# tiny_robot_renew.net
KiCad netlist of a schematic drawn in EAGLE
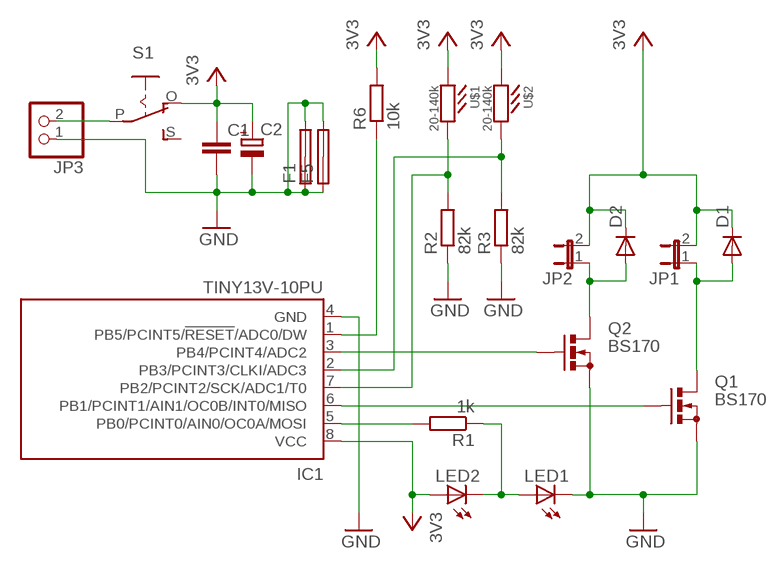
[diagram p0: schematic, sheet 1]

(export (version "E")
  (design (tool "Eeschema 10.0.6"))
  (components
    (comp (ref "C1")
      (value "C-EU025-025X050")
      (footprint "eagle-import:C025-025X050")
      (libsource (lib "eagle-import") (part "C-EU025-025X050"))
    )
    (comp (ref "C2")
      (value "CPOL-EUE2,5-6E")
      (footprint "eagle-import:E2,5-6E")
      (libsource (lib "eagle-import") (part "CPOL-EUE2,5-6E"))
    )
    (comp (ref "D1")
      (value "DIODE-D-2.5")
      (footprint "eagle-import:D-2.5")
      (libsource (lib "eagle-import") (part "DIODE-D-2.5"))
    )
    (comp (ref "D2")
      (value "DIODE-D-2.5")
      (footprint "eagle-import:D-2.5")
      (libsource (lib "eagle-import") (part "DIODE-D-2.5"))
    )
    (comp (ref "F1")
      (value "SHK20L")
      (footprint "eagle-import:SHK20L")
      (libsource (lib "eagle-import") (part "SHK20L"))
    )
    (comp (ref "F5")
      (value "SHK20Q")
      (footprint "eagle-import:SHK20Q")
      (libsource (lib "eagle-import") (part "SHK20Q"))
    )
    (comp (ref "IC1")
      (value "TINY13V-10PU")
      (footprint "eagle-import:DIL08")
      (fields (field (name "MPN") "ATTINY13V-10PU"))
      (libsource (lib "eagle-import") (part "TINY13PUV-10"))
    )
    (comp (ref "JP1")
      (value "JP1E")
      (footprint "eagle-import:JP1")
      (libsource (lib "eagle-import") (part "JP1E"))
    )
    (comp (ref "JP2")
      (value "JP1E")
      (footprint "eagle-import:JP1")
      (libsource (lib "eagle-import") (part "JP1E"))
    )
    (comp (ref "JP3")
      (value "PINHD-1X2")
      (footprint "eagle-import:1X02")
      (libsource (lib "eagle-import") (part "PINHD-1X2"))
    )
    (comp (ref "LED1")
      (value "LED3MM")
      (footprint "eagle-import:LED3MM")
      (libsource (lib "eagle-import") (part "LED3MM"))
    )
    (comp (ref "LED2")
      (value "LED3MM")
      (footprint "eagle-import:LED3MM")
      (libsource (lib "eagle-import") (part "LED3MM"))
    )
    (comp (ref "Q1")
      (value "BS170")
      (footprint "eagle-import:SOT54E")
      (libsource (lib "eagle-import") (part "BS170"))
    )
    (comp (ref "Q2")
      (value "BS170")
      (footprint "eagle-import:SOT54E")
      (libsource (lib "eagle-import") (part "BS170"))
    )
    (comp (ref "R1")
      (value "1k")
      (footprint "eagle-import:0204_7")
      (libsource (lib "eagle-import") (part "R-EU_0204/7"))
    )
    (comp (ref "R2")
      (value "82k")
      (footprint "eagle-import:0207_2V")
      (libsource (lib "eagle-import") (part "R-EU_0207/2V"))
    )
    (comp (ref "R3")
      (value "82k")
      (footprint "eagle-import:0207_2V")
      (libsource (lib "eagle-import") (part "R-EU_0207/2V"))
    )
    (comp (ref "R6")
      (value "10k")
      (footprint "eagle-import:0204_7")
      (libsource (lib "eagle-import") (part "R-EU_0204/7"))
    )
    (comp (ref "S1")
      (value "EG1218S")
      (footprint "eagle-import:EG1218")
      (libsource (lib "eagle-import") (part "EG1218S"))
    )
    (comp (ref "U$1")
      (value "20-140k")
      (footprint "eagle-import:LDR-906014")
      (libsource (lib "eagle-import") (part "LDR-906014"))
    )
    (comp (ref "U$2")
      (value "20-140k")
      (footprint "eagle-import:LDR-906014")
      (libsource (lib "eagle-import") (part "LDR-906014"))
    )
  )
  (nets
    (net (code "1") (name "3V3") (class "Default")
      (node (ref "C1") (pin "1") (pinfunction "1_1") (pintype "passive"))
      (node (ref "C2") (pin "+") (pinfunction "+_+") (pintype "passive"))
      (node (ref "D1") (pin "C") (pinfunction "C_C") (pintype "passive"))
      (node (ref "D2") (pin "C") (pinfunction "C_C") (pintype "passive"))
      (node (ref "IC1") (pin "8") (pinfunction "VCC_8") (pintype "power_in"))
      (node (ref "JP1") (pin "2") (pinfunction "2_2") (pintype "passive"))
      (node (ref "JP2") (pin "2") (pinfunction "2_2") (pintype "passive"))
      (node (ref "LED2") (pin "A") (pinfunction "A_A") (pintype "passive"))
      (node (ref "R6") (pin "2") (pinfunction "2_2") (pintype "passive"))
      (node (ref "S1") (pin "O") (pinfunction "O_O") (pintype "passive"))
      (node (ref "U$1") (pin "P$1") (pinfunction "P$1_P$1") (pintype "passive"))
      (node (ref "U$2") (pin "P$1") (pinfunction "P$1_P$1") (pintype "passive"))
    )
    (net (code "2") (name "GND") (class "Default")
      (node (ref "C1") (pin "2") (pinfunction "2_2") (pintype "passive"))
      (node (ref "C2") (pin "-") (pinfunction "-_-") (pintype "passive"))
      (node (ref "F1") (pin "1A") (pinfunction "1A_1A") (pintype "passive"))
      (node (ref "F1") (pin "2A") (pinfunction "2A_2A") (pintype "passive"))
      (node (ref "F5") (pin "1A") (pinfunction "1A_1A") (pintype "passive"))
      (node (ref "F5") (pin "2A") (pinfunction "2A_2A") (pintype "passive"))
      (node (ref "IC1") (pin "4") (pinfunction "GND_4") (pintype "power_in"))
      (node (ref "JP3") (pin "1") (pinfunction "1_1") (pintype "passive"))
      (node (ref "LED1") (pin "K") (pinfunction "C_K") (pintype "passive"))
      (node (ref "Q1") (pin "S") (pinfunction "S_S") (pintype "passive"))
      (node (ref "Q2") (pin "S") (pinfunction "S_S") (pintype "passive"))
      (node (ref "R2") (pin "1") (pinfunction "1_1") (pintype "passive"))
      (node (ref "R3") (pin "1") (pinfunction "1_1") (pintype "passive"))
    )
    (net (code "3") (name "Net-(D1-PadA)") (class "Default")
      (node (ref "D1") (pin "A") (pinfunction "A_A") (pintype "passive"))
      (node (ref "JP1") (pin "1") (pinfunction "1_1") (pintype "passive"))
      (node (ref "Q1") (pin "D") (pinfunction "D_D") (pintype "passive"))
    )
    (net (code "4") (name "Net-(D2-PadA)") (class "Default")
      (node (ref "D2") (pin "A") (pinfunction "A_A") (pintype "passive"))
      (node (ref "JP2") (pin "1") (pinfunction "1_1") (pintype "passive"))
      (node (ref "Q2") (pin "D") (pinfunction "D_D") (pintype "passive"))
    )
    (net (code "5") (name "Net-(IC1-PB0{slash}PCINT0{slash}AIN0{slash}OC0A{slash}MOSI)") (class "Default")
      (node (ref "IC1") (pin "5") (pinfunction "PB0/PCINT0/AIN0/OC0A/MOSI_5") (pintype "bidirectional"))
      (node (ref "R1") (pin "2") (pinfunction "2_2") (pintype "passive"))
    )
    (net (code "6") (name "Net-(IC1-PB1{slash}PCINT1{slash}AIN1{slash}OC0B{slash}INT0{slash}MISO)") (class "Default")
      (node (ref "IC1") (pin "6") (pinfunction "PB1/PCINT1/AIN1/OC0B/INT0/MISO_6") (pintype "bidirectional"))
      (node (ref "Q1") (pin "G") (pinfunction "G_G") (pintype "passive"))
    )
    (net (code "7") (name "Net-(IC1-PB2{slash}PCINT2{slash}SCK{slash}ADC1{slash}T0)") (class "Default")
      (node (ref "IC1") (pin "7") (pinfunction "PB2/PCINT2/SCK/ADC1/T0_7") (pintype "bidirectional"))
      (node (ref "R2") (pin "2") (pinfunction "2_2") (pintype "passive"))
      (node (ref "U$1") (pin "P$2") (pinfunction "P$2_P$2") (pintype "passive"))
    )
    (net (code "8") (name "Net-(IC1-PB3{slash}PCINT3{slash}CLKI{slash}ADC3)") (class "Default")
      (node (ref "IC1") (pin "2") (pinfunction "PB3/PCINT3/CLKI/ADC3_2") (pintype "bidirectional"))
      (node (ref "R3") (pin "2") (pinfunction "2_2") (pintype "passive"))
      (node (ref "U$2") (pin "P$2") (pinfunction "P$2_P$2") (pintype "passive"))
    )
    (net (code "9") (name "Net-(IC1-PB4{slash}PCINT4{slash}ADC2)") (class "Default")
      (node (ref "IC1") (pin "3") (pinfunction "PB4/PCINT4/ADC2_3") (pintype "bidirectional"))
      (node (ref "Q2") (pin "G") (pinfunction "G_G") (pintype "passive"))
    )
    (net (code "10") (name "Net-(IC1-PB5{slash}PCINT5{slash}~{RESET}{slash}ADC0{slash}DW)") (class "Default")
      (node (ref "IC1") (pin "1") (pinfunction "PB5/PCINT5/~{RESET}/ADC0/DW_1") (pintype "bidirectional"))
      (node (ref "R6") (pin "1") (pinfunction "1_1") (pintype "passive"))
    )
    (net (code "11") (name "Net-(JP3-Pad2)") (class "Default")
      (node (ref "JP3") (pin "2") (pinfunction "2_2") (pintype "passive"))
      (node (ref "S1") (pin "P") (pinfunction "P_P") (pintype "passive"))
    )
    (net (code "12") (name "Net-(LED2-C)") (class "Default")
      (node (ref "LED1") (pin "A") (pinfunction "A_A") (pintype "passive"))
      (node (ref "LED2") (pin "K") (pinfunction "C_K") (pintype "passive"))
      (node (ref "R1") (pin "1") (pinfunction "1_1") (pintype "passive"))
    )
    (net (code "13") (name "unconnected-(F1-Pad1B)") (class "Default")
      (node (ref "F1") (pin "1B") (pinfunction "1B_1B") (pintype "passive"))
    )
    (net (code "14") (name "unconnected-(F1-Pad2B)") (class "Default")
      (node (ref "F1") (pin "2B") (pinfunction "2B_2B") (pintype "passive"))
    )
    (net (code "15") (name "unconnected-(F5-Pad1B)") (class "Default")
      (node (ref "F5") (pin "1B") (pinfunction "1B_1B") (pintype "passive"))
    )
    (net (code "16") (name "unconnected-(F5-Pad2B)") (class "Default")
      (node (ref "F5") (pin "2B") (pinfunction "2B_2B") (pintype "passive"))
    )
    (net (code "17") (name "unconnected-(S1-PadS)") (class "Default")
      (node (ref "S1") (pin "S") (pinfunction "S_S") (pintype "passive"))
    )
  )
)
